# PWR.net
KiCad netlist of a schematic drawn in Altium Designer
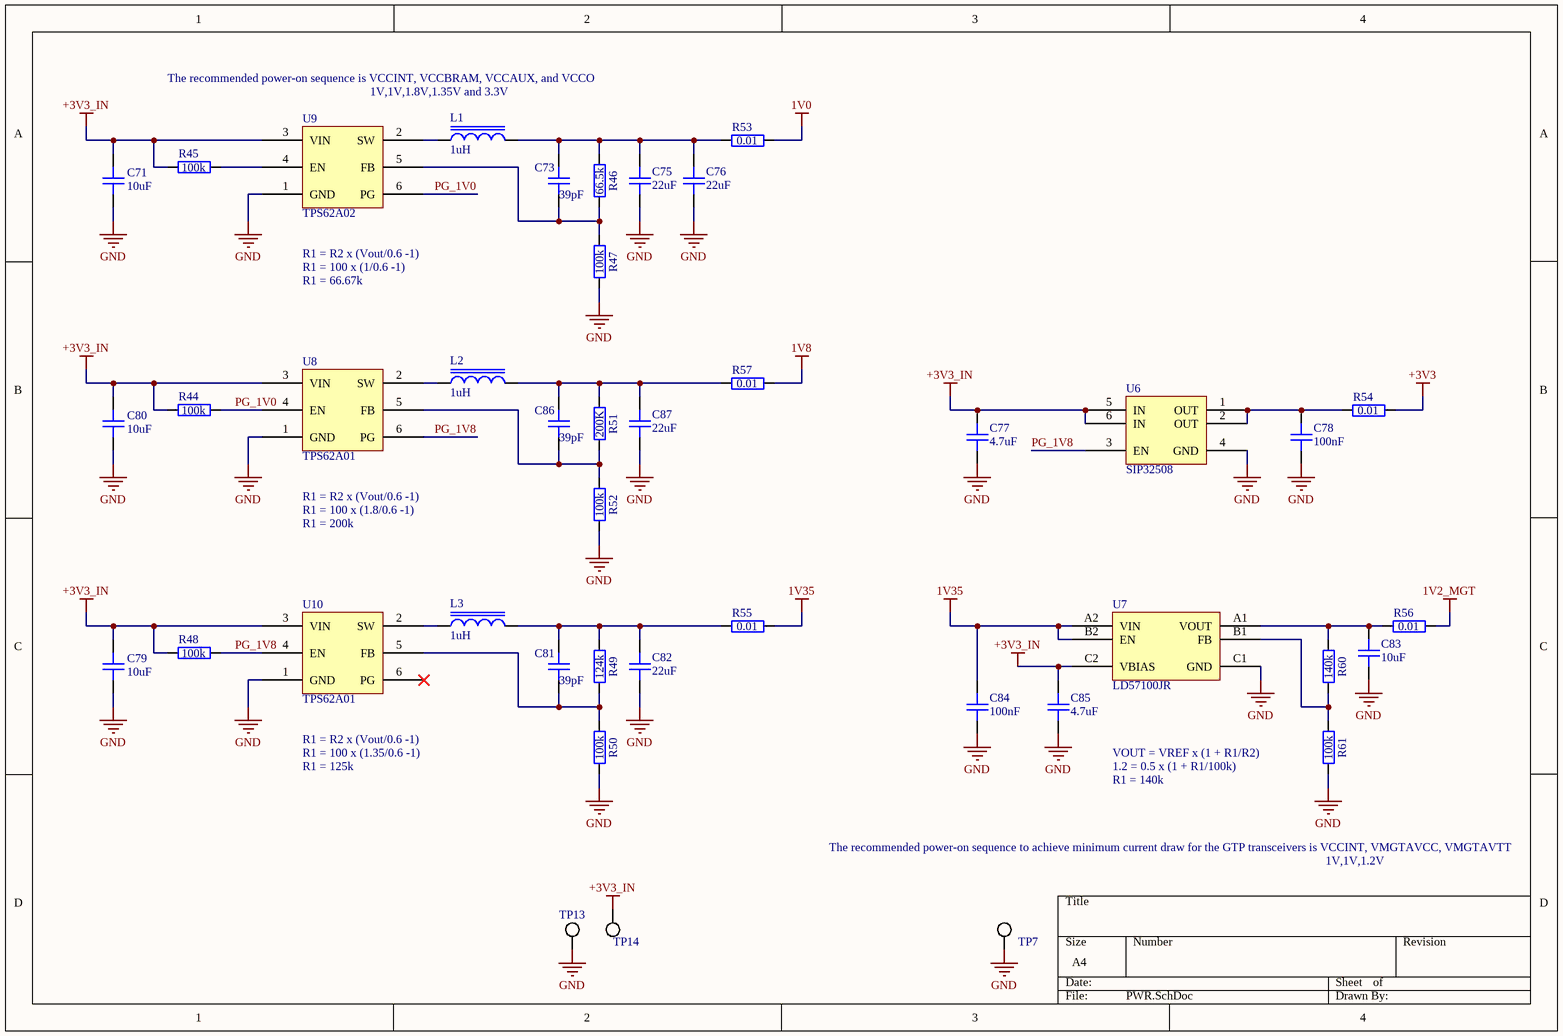
[diagram p0: PWR.SchDoc]

(export (version "E")
  (design (tool "Eeschema 10.0.6"))
  (components
    (comp (ref "C71")
      (value "10uF")
      (footprint "GEN_C_0603")
      (fields
        (field (name "HOUSE PART NUMBER") "C-10uF-0603-002")
        (field (name "MANUFACTURER") "Murata")
        (field (name "MANUFACTURER PART NUMBER") "GRM188R61A106ME69D")
      )
      (libsource (lib "DSO") (part "CAP 10uF 10V X5R 0603"))
    )
    (comp (ref "C73")
      (value "39pF")
      (footprint "GEN_C_0402")
      (fields
        (field (name "HOUSE PART NUMBER") "C-39pF-0402-002")
        (field (name "MANUFACTURER") "KEMET")
        (field (name "MANUFACTURER PART NUMBER") "C0402C390J5GACTU")
      )
      (libsource (lib "DSO") (part "CAP 39pF 50V C0G 0402"))
    )
    (comp (ref "C75")
      (value "22uF")
      (footprint "GEN_C_0805")
      (fields
        (field (name "HOUSE PART NUMBER") "C-22uF-0805-002")
        (field (name "MANUFACTURER") "Murata")
        (field (name "MANUFACTURER PART NUMBER") "GRM21BR61E226ME44L")
      )
      (libsource (lib "DSO") (part "CAP 22uF 25V X5R 0805"))
    )
    (comp (ref "C76")
      (value "22uF")
      (footprint "GEN_C_0805")
      (fields
        (field (name "HOUSE PART NUMBER") "C-22uF-0805-002")
        (field (name "MANUFACTURER") "Murata")
        (field (name "MANUFACTURER PART NUMBER") "GRM21BR61E226ME44L")
      )
      (libsource (lib "DSO") (part "CAP 22uF 25V X5R 0805"))
    )
    (comp (ref "C77")
      (value "4.7uF")
      (footprint "GEN_C_0402")
      (fields
        (field (name "HOUSE PART NUMBER") "C-4.7uF-0402-002")
        (field (name "MANUFACTURER") "Murata")
        (field (name "MANUFACTURER PART NUMBER") "GRM155R60J475ME47D")
      )
      (libsource (lib "DSO") (part "CAP 4.7uF 6.3V X5R 0402"))
    )
    (comp (ref "C78")
      (value "100nF")
      (footprint "GEN_C_0402")
      (fields
        (field (name "HOUSE PART NUMBER") "C-100nF-0402-002")
        (field (name "MANUFACTURER") "Murata")
        (field (name "MANUFACTURER PART NUMBER") "GCM155R71C104KA55D")
      )
      (libsource (lib "DSO") (part "CAP 100nF 16V X7R 0402"))
    )
    (comp (ref "C79")
      (value "10uF")
      (footprint "GEN_C_0603")
      (fields
        (field (name "HOUSE PART NUMBER") "C-10uF-0603-002")
        (field (name "MANUFACTURER") "Murata")
        (field (name "MANUFACTURER PART NUMBER") "GRM188R61A106ME69D")
      )
      (libsource (lib "DSO") (part "CAP 10uF 10V X5R 0603"))
    )
    (comp (ref "C80")
      (value "10uF")
      (footprint "GEN_C_0603")
      (fields
        (field (name "HOUSE PART NUMBER") "C-10uF-0603-002")
        (field (name "MANUFACTURER") "Murata")
        (field (name "MANUFACTURER PART NUMBER") "GRM188R61A106ME69D")
      )
      (libsource (lib "DSO") (part "CAP 10uF 10V X5R 0603"))
    )
    (comp (ref "C81")
      (value "39pF")
      (footprint "GEN_C_0402")
      (fields
        (field (name "HOUSE PART NUMBER") "C-39pF-0402-002")
        (field (name "MANUFACTURER") "KEMET")
        (field (name "MANUFACTURER PART NUMBER") "C0402C390J5GACTU")
      )
      (libsource (lib "DSO") (part "CAP 39pF 50V C0G 0402"))
    )
    (comp (ref "C82")
      (value "22uF")
      (footprint "GEN_C_0805")
      (fields
        (field (name "HOUSE PART NUMBER") "C-22uF-0805-002")
        (field (name "MANUFACTURER") "Murata")
        (field (name "MANUFACTURER PART NUMBER") "GRM21BR61E226ME44L")
      )
      (libsource (lib "DSO") (part "CAP 22uF 25V X5R 0805"))
    )
    (comp (ref "C83")
      (value "10uF")
      (footprint "GEN_C_0603")
      (fields
        (field (name "HOUSE PART NUMBER") "C-10uF-0603-002")
        (field (name "MANUFACTURER") "Murata")
        (field (name "MANUFACTURER PART NUMBER") "GRM188R61A106ME69D")
      )
      (libsource (lib "DSO") (part "CAP 10uF 10V X5R 0603"))
    )
    (comp (ref "C84")
      (value "100nF")
      (footprint "GEN_C_0402")
      (fields
        (field (name "HOUSE PART NUMBER") "C-100nF-0402-002")
        (field (name "MANUFACTURER") "Murata")
        (field (name "MANUFACTURER PART NUMBER") "GCM155R71C104KA55D")
      )
      (libsource (lib "DSO") (part "CAP 100nF 16V X7R 0402"))
    )
    (comp (ref "C85")
      (value "4.7uF")
      (footprint "GEN_C_0402")
      (fields
        (field (name "HOUSE PART NUMBER") "C-4.7uF-0402-002")
        (field (name "MANUFACTURER") "Murata")
        (field (name "MANUFACTURER PART NUMBER") "GRM155R60J475ME47D")
      )
      (libsource (lib "DSO") (part "CAP 4.7uF 6.3V X5R 0402"))
    )
    (comp (ref "C86")
      (value "39pF")
      (footprint "GEN_C_0402")
      (fields
        (field (name "HOUSE PART NUMBER") "C-39pF-0402-002")
        (field (name "MANUFACTURER") "KEMET")
        (field (name "MANUFACTURER PART NUMBER") "C0402C390J5GACTU")
      )
      (libsource (lib "DSO") (part "CAP 39pF 50V C0G 0402"))
    )
    (comp (ref "C87")
      (value "22uF")
      (footprint "GEN_C_0805")
      (fields
        (field (name "HOUSE PART NUMBER") "C-22uF-0805-002")
        (field (name "MANUFACTURER") "Murata")
        (field (name "MANUFACTURER PART NUMBER") "GRM21BR61E226ME44L")
      )
      (libsource (lib "DSO") (part "CAP 22uF 25V X5R 0805"))
    )
    (comp (ref "L1")
      (value "1uH")
      (footprint "GEN_L_1210")
      (fields (field (name "HOUSE PART NUMBER") "SRP3212-1R0M") (field (name "MANUFACTURER") "Bourns"))
      (libsource (lib "DSO") (part "IND 1uH 5.5A 32 MOHM 1210"))
    )
    (comp (ref "L2")
      (value "1uH")
      (footprint "GEN_L_1210")
      (fields (field (name "HOUSE PART NUMBER") "SRP3212-1R0M") (field (name "MANUFACTURER") "Bourns"))
      (libsource (lib "DSO") (part "IND 1uH 5.5A 32 MOHM 1210"))
    )
    (comp (ref "L3")
      (value "1uH")
      (footprint "GEN_L_1210")
      (fields (field (name "HOUSE PART NUMBER") "SRP3212-1R0M") (field (name "MANUFACTURER") "Bourns"))
      (libsource (lib "DSO") (part "IND 1uH 5.5A 32 MOHM 1210"))
    )
    (comp (ref "R44")
      (value "100k")
      (footprint "GEN_R_0402")
      (fields
        (field (name "TOLERANCE") "1%")
        (field (name "HOUSE PART NUMBER") "R-100K-0402-1%-001")
        (field (name "MANUFACTURER") "Yageo")
      )
      (libsource (lib "") (part "RES 100K OHM 1% 1/10W 0402_1"))
    )
    (comp (ref "R45")
      (value "100k")
      (footprint "GEN_R_0402")
      (fields
        (field (name "TOLERANCE") "1%")
        (field (name "HOUSE PART NUMBER") "R-100K-0402-1%-001")
        (field (name "MANUFACTURER") "Yageo")
      )
      (libsource (lib "") (part "RES 100K OHM 1% 1/10W 0402_1"))
    )
    (comp (ref "R46")
      (value "66.5k")
      (footprint "GEN_R_0402")
      (fields
        (field (name "TOLERANCE") "1%")
        (field (name "HOUSE PART NUMBER") "R-66.5K-0402-1%-001")
        (field (name "MANUFACTURER") "Yageo")
      )
      (libsource (lib "DSO") (part "RES 66.5K OHM 1% 1/16W 0402"))
    )
    (comp (ref "R47")
      (value "100k")
      (footprint "GEN_R_0402")
      (fields
        (field (name "TOLERANCE") "1%")
        (field (name "HOUSE PART NUMBER") "R-100K-0402-1%-001")
        (field (name "MANUFACTURER") "Yageo")
      )
      (libsource (lib "DSO") (part "RES 100K OHM 1% 1/10W 0402"))
    )
    (comp (ref "R48")
      (value "100k")
      (footprint "GEN_R_0402")
      (fields
        (field (name "TOLERANCE") "1%")
        (field (name "HOUSE PART NUMBER") "R-100K-0402-1%-001")
        (field (name "MANUFACTURER") "Yageo")
      )
      (libsource (lib "") (part "RES 100K OHM 1% 1/10W 0402_1"))
    )
    (comp (ref "R49")
      (value "124k")
      (footprint "GEN_R_0402")
      (fields
        (field (name "TOLERANCE") "1%")
        (field (name "HOUSE PART NUMBER") "R-124K-0402-1%-001")
        (field (name "MANUFACTURER") "Yageo")
      )
      (libsource (lib "DSO") (part "RES 124K OHM 1% 1/10W 0402"))
    )
    (comp (ref "R50")
      (value "100k")
      (footprint "GEN_R_0402")
      (fields
        (field (name "TOLERANCE") "1%")
        (field (name "HOUSE PART NUMBER") "R-100K-0402-1%-001")
        (field (name "MANUFACTURER") "Yageo")
      )
      (libsource (lib "DSO") (part "RES 100K OHM 1% 1/10W 0402"))
    )
    (comp (ref "R51")
      (value "200K")
      (footprint "GEN_R_0402")
      (fields
        (field (name "TOLERANCE") "1%")
        (field (name "HOUSE PART NUMBER") "R-200K-0402-1%-001")
        (field (name "MANUFACTURER") "Yageo")
      )
      (libsource (lib "DSO") (part "RES 200K OHM 1% 1/16W 0402"))
    )
    (comp (ref "R52")
      (value "100k")
      (footprint "GEN_R_0402")
      (fields
        (field (name "TOLERANCE") "1%")
        (field (name "HOUSE PART NUMBER") "R-100K-0402-1%-001")
        (field (name "MANUFACTURER") "Yageo")
      )
      (libsource (lib "DSO") (part "RES 100K OHM 1% 1/10W 0402"))
    )
    (comp (ref "R53")
      (value "0.01")
      (footprint "GEN_R_0603")
      (fields
        (field (name "TOLERANCE") "1%")
        (field (name "HOUSE PART NUMBER") "R-0.01-0603-1%-001")
        (field (name "MANUFACTURER") "Susumu")
      )
      (libsource (lib "DSO") (part "RES 0.01 OHM 1% 1/4W 0603"))
    )
    (comp (ref "R54")
      (value "0.01")
      (footprint "GEN_R_0603")
      (fields
        (field (name "TOLERANCE") "1%")
        (field (name "HOUSE PART NUMBER") "R-0.01-0603-1%-001")
        (field (name "MANUFACTURER") "Susumu")
      )
      (libsource (lib "DSO") (part "RES 0.01 OHM 1% 1/4W 0603"))
    )
    (comp (ref "R55")
      (value "0.01")
      (footprint "GEN_R_0603")
      (fields
        (field (name "TOLERANCE") "1%")
        (field (name "HOUSE PART NUMBER") "R-0.01-0603-1%-001")
        (field (name "MANUFACTURER") "Susumu")
      )
      (libsource (lib "DSO") (part "RES 0.01 OHM 1% 1/4W 0603"))
    )
    (comp (ref "R56")
      (value "0.01")
      (footprint "GEN_R_0603")
      (fields
        (field (name "TOLERANCE") "1%")
        (field (name "HOUSE PART NUMBER") "R-0.01-0603-1%-001")
        (field (name "MANUFACTURER") "Susumu")
      )
      (libsource (lib "DSO") (part "RES 0.01 OHM 1% 1/4W 0603"))
    )
    (comp (ref "R57")
      (value "0.01")
      (footprint "GEN_R_0603")
      (fields
        (field (name "TOLERANCE") "1%")
        (field (name "HOUSE PART NUMBER") "R-0.01-0603-1%-001")
        (field (name "MANUFACTURER") "Susumu")
      )
      (libsource (lib "DSO") (part "RES 0.01 OHM 1% 1/4W 0603"))
    )
    (comp (ref "R60")
      (value "140k")
      (footprint "GEN_R_0402")
      (fields
        (field (name "TOLERANCE") "1%")
        (field (name "HOUSE PART NUMBER") "R-140K-0402-1%-001")
        (field (name "MANUFACTURER") "Yageo")
      )
      (libsource (lib "DSO") (part "RES 140K OHM 1% 1/10W 0402"))
    )
    (comp (ref "R61")
      (value "100k")
      (footprint "GEN_R_0402")
      (fields
        (field (name "TOLERANCE") "1%")
        (field (name "HOUSE PART NUMBER") "R-100K-0402-1%-001")
        (field (name "MANUFACTURER") "Yageo")
      )
      (libsource (lib "DSO") (part "RES 100K OHM 1% 1/10W 0402"))
    )
    (comp (ref "TP7") (value "PCB") (footprint "GEN_TP_PCB") (libsource (lib "DSO") (part "TP PCB 1mm")))
    (comp (ref "TP13") (value "PCB") (footprint "GEN_TP_PCB") (libsource (lib "DSO") (part "TP PCB 1mm")))
    (comp (ref "TP14") (value "PCB") (footprint "GEN_TP_PCB") (libsource (lib "DSO") (part "TP PCB 1mm")))
    (comp (ref "U6")
      (value "SIP32508")
      (footprint "VISH_TSOT6")
      (fields
        (field (name "MANUFACTURER") "Vishay Siliconix")
        (field (name "MANUFACTURER PART NUMBER") "SIP32508DT-T1-GE3")
      )
      (libsource (lib "DSO") (part "IC SWITCH LOAD SIP32508"))
    )
    (comp (ref "U7")
      (value "LD57100JR")
      (footprint "ST_FlipChip6")
      (fields (field (name "MANUFACTURER") "STMicroelectronics"))
      (libsource (lib "DSO") (part "IC LDO LD57100JR"))
    )
    (comp (ref "U8")
      (value "TPS62A01")
      (footprint "TI_SOT563_DRL0006A")
      (fields
        (field (name "HOUSE PART NUMBER") "TPS62A01DRLR")
        (field (name "MANUFACTURER") "Texas Instruments")
      )
      (libsource (lib "DSO") (part "IC BUCK TPS62A01"))
    )
    (comp (ref "U9")
      (value "TPS62A02")
      (footprint "TI_SOT563_DRL0006A")
      (fields
        (field (name "HOUSE PART NUMBER") "TPS62A02DRLR")
        (field (name "MANUFACTURER") "Texas Instruments")
      )
      (libsource (lib "DSO") (part "IC BUCK TPS62A02"))
    )
    (comp (ref "U10")
      (value "TPS62A01")
      (footprint "TI_SOT563_DRL0006A")
      (fields
        (field (name "HOUSE PART NUMBER") "TPS62A01DRLR")
        (field (name "MANUFACTURER") "Texas Instruments")
      )
      (libsource (lib "DSO") (part "IC BUCK TPS62A01"))
    )
  )
  (nets
    (net (code "1") (name "+3V3") (class "Default")
      (node (ref "R54") (pin "2") (pinfunction "2_2") (pintype "passive"))
    )
    (net (code "2") (name "+3V3_IN") (class "Default")
      (node (ref "C71") (pin "2") (pinfunction "2_2") (pintype "passive"))
      (node (ref "C77") (pin "2") (pinfunction "2_2") (pintype "passive"))
      (node (ref "C79") (pin "2") (pinfunction "2_2") (pintype "passive"))
      (node (ref "C80") (pin "2") (pinfunction "2_2") (pintype "passive"))
      (node (ref "C85") (pin "2") (pinfunction "2_2") (pintype "passive"))
      (node (ref "R44") (pin "2") (pinfunction "2_2") (pintype "passive"))
      (node (ref "R45") (pin "2") (pinfunction "2_2") (pintype "passive"))
      (node (ref "R48") (pin "2") (pinfunction "2_2") (pintype "passive"))
      (node (ref "TP14") (pin "1") (pinfunction "1_1") (pintype "passive"))
      (node (ref "U10") (pin "3") (pinfunction "VIN_3") (pintype "power_in"))
      (node (ref "U6") (pin "5") (pinfunction "IN_5") (pintype "passive"))
      (node (ref "U6") (pin "6") (pinfunction "IN_6") (pintype "passive"))
      (node (ref "U7") (pin "C2") (pinfunction "VBIAS_C2") (pintype "passive"))
      (node (ref "U8") (pin "3") (pinfunction "VIN_3") (pintype "power_in"))
      (node (ref "U9") (pin "3") (pinfunction "VIN_3") (pintype "power_in"))
    )
    (net (code "3") (name "/PG_1V0") (class "Default")
      (node (ref "R44") (pin "1") (pinfunction "1_1") (pintype "passive"))
      (node (ref "U8") (pin "4") (pinfunction "EN_4") (pintype "passive"))
      (node (ref "U9") (pin "6") (pinfunction "PG_6") (pintype "passive"))
    )
    (net (code "4") (name "/PG_1V8") (class "Default")
      (node (ref "R48") (pin "1") (pinfunction "1_1") (pintype "passive"))
      (node (ref "U10") (pin "4") (pinfunction "EN_4") (pintype "passive"))
      (node (ref "U6") (pin "3") (pinfunction "EN_3") (pintype "passive"))
      (node (ref "U8") (pin "6") (pinfunction "PG_6") (pintype "passive"))
    )
    (net (code "5") (name "1V0") (class "Default")
      (node (ref "R53") (pin "2") (pinfunction "2_2") (pintype "passive"))
    )
    (net (code "6") (name "1V2_MGT") (class "Default")
      (node (ref "R56") (pin "2") (pinfunction "2_2") (pintype "passive"))
    )
    (net (code "7") (name "1V8") (class "Default")
      (node (ref "R57") (pin "2") (pinfunction "2_2") (pintype "passive"))
    )
    (net (code "8") (name "1V35") (class "Default")
      (node (ref "C84") (pin "2") (pinfunction "2_2") (pintype "passive"))
      (node (ref "R55") (pin "2") (pinfunction "2_2") (pintype "passive"))
      (node (ref "U7") (pin "A2") (pinfunction "VIN_A2") (pintype "passive"))
      (node (ref "U7") (pin "B2") (pinfunction "EN_B2") (pintype "passive"))
    )
    (net (code "9") (name "GND") (class "Default")
      (node (ref "C71") (pin "1") (pinfunction "1_1") (pintype "passive"))
      (node (ref "C75") (pin "1") (pinfunction "1_1") (pintype "passive"))
      (node (ref "C76") (pin "1") (pinfunction "1_1") (pintype "passive"))
      (node (ref "C77") (pin "1") (pinfunction "1_1") (pintype "passive"))
      (node (ref "C78") (pin "1") (pinfunction "1_1") (pintype "passive"))
      (node (ref "C79") (pin "1") (pinfunction "1_1") (pintype "passive"))
      (node (ref "C80") (pin "1") (pinfunction "1_1") (pintype "passive"))
      (node (ref "C82") (pin "1") (pinfunction "1_1") (pintype "passive"))
      (node (ref "C83") (pin "1") (pinfunction "1_1") (pintype "passive"))
      (node (ref "C84") (pin "1") (pinfunction "1_1") (pintype "passive"))
      (node (ref "C85") (pin "1") (pinfunction "1_1") (pintype "passive"))
      (node (ref "C87") (pin "1") (pinfunction "1_1") (pintype "passive"))
      (node (ref "R47") (pin "1") (pinfunction "1_1") (pintype "passive"))
      (node (ref "R50") (pin "1") (pinfunction "1_1") (pintype "passive"))
      (node (ref "R52") (pin "1") (pinfunction "1_1") (pintype "passive"))
      (node (ref "R61") (pin "1") (pinfunction "1_1") (pintype "passive"))
      (node (ref "TP13") (pin "1") (pinfunction "1_1") (pintype "passive"))
      (node (ref "TP7") (pin "1") (pinfunction "1_1") (pintype "passive"))
      (node (ref "U10") (pin "1") (pinfunction "GND_1") (pintype "power_in"))
      (node (ref "U6") (pin "4") (pinfunction "GND_4") (pintype "passive"))
      (node (ref "U7") (pin "C1") (pinfunction "GND_C1") (pintype "passive"))
      (node (ref "U8") (pin "1") (pinfunction "GND_1") (pintype "power_in"))
      (node (ref "U9") (pin "1") (pinfunction "GND_1") (pintype "power_in"))
    )
    (net (code "10") (name "Net-(C73-Pad2)") (class "Default")
      (node (ref "C73") (pin "2") (pinfunction "2_2") (pintype "passive"))
      (node (ref "C75") (pin "2") (pinfunction "2_2") (pintype "passive"))
      (node (ref "C76") (pin "2") (pinfunction "2_2") (pintype "passive"))
      (node (ref "L1") (pin "2") (pinfunction "2_2") (pintype "passive"))
      (node (ref "R46") (pin "2") (pinfunction "2_2") (pintype "passive"))
      (node (ref "R53") (pin "1") (pinfunction "1_1") (pintype "passive"))
    )
    (net (code "11") (name "Net-(C78-Pad2)") (class "Default")
      (node (ref "C78") (pin "2") (pinfunction "2_2") (pintype "passive"))
      (node (ref "R54") (pin "1") (pinfunction "1_1") (pintype "passive"))
      (node (ref "U6") (pin "1") (pinfunction "OUT_1") (pintype "passive"))
      (node (ref "U6") (pin "2") (pinfunction "OUT_2") (pintype "passive"))
    )
    (net (code "12") (name "Net-(C81-Pad2)") (class "Default")
      (node (ref "C81") (pin "2") (pinfunction "2_2") (pintype "passive"))
      (node (ref "C82") (pin "2") (pinfunction "2_2") (pintype "passive"))
      (node (ref "L3") (pin "2") (pinfunction "2_2") (pintype "passive"))
      (node (ref "R49") (pin "2") (pinfunction "2_2") (pintype "passive"))
      (node (ref "R55") (pin "1") (pinfunction "1_1") (pintype "passive"))
    )
    (net (code "13") (name "Net-(C86-Pad2)") (class "Default")
      (node (ref "C86") (pin "2") (pinfunction "2_2") (pintype "passive"))
      (node (ref "C87") (pin "2") (pinfunction "2_2") (pintype "passive"))
      (node (ref "L2") (pin "2") (pinfunction "2_2") (pintype "passive"))
      (node (ref "R51") (pin "2") (pinfunction "2_2") (pintype "passive"))
      (node (ref "R57") (pin "1") (pinfunction "1_1") (pintype "passive"))
    )
    (net (code "14") (name "Net-(U7-FB)") (class "Default")
      (node (ref "R60") (pin "1") (pinfunction "1_1") (pintype "passive"))
      (node (ref "R61") (pin "2") (pinfunction "2_2") (pintype "passive"))
      (node (ref "U7") (pin "B1") (pinfunction "FB_B1") (pintype "passive"))
    )
    (net (code "15") (name "Net-(U7-VOUT)") (class "Default")
      (node (ref "C83") (pin "2") (pinfunction "2_2") (pintype "passive"))
      (node (ref "R56") (pin "1") (pinfunction "1_1") (pintype "passive"))
      (node (ref "R60") (pin "2") (pinfunction "2_2") (pintype "passive"))
      (node (ref "U7") (pin "A1") (pinfunction "VOUT_A1") (pintype "passive"))
    )
    (net (code "16") (name "Net-(U8-FB)") (class "Default")
      (node (ref "C86") (pin "1") (pinfunction "1_1") (pintype "passive"))
      (node (ref "R51") (pin "1") (pinfunction "1_1") (pintype "passive"))
      (node (ref "R52") (pin "2") (pinfunction "2_2") (pintype "passive"))
      (node (ref "U8") (pin "5") (pinfunction "FB_5") (pintype "passive"))
    )
    (net (code "17") (name "Net-(U8-SW)") (class "Default")
      (node (ref "L2") (pin "1") (pinfunction "1_1") (pintype "passive"))
      (node (ref "U8") (pin "2") (pinfunction "SW_2") (pintype "passive"))
    )
    (net (code "18") (name "Net-(U9-EN)") (class "Default")
      (node (ref "R45") (pin "1") (pinfunction "1_1") (pintype "passive"))
      (node (ref "U9") (pin "4") (pinfunction "EN_4") (pintype "passive"))
    )
    (net (code "19") (name "Net-(U9-FB)") (class "Default")
      (node (ref "C73") (pin "1") (pinfunction "1_1") (pintype "passive"))
      (node (ref "R46") (pin "1") (pinfunction "1_1") (pintype "passive"))
      (node (ref "R47") (pin "2") (pinfunction "2_2") (pintype "passive"))
      (node (ref "U9") (pin "5") (pinfunction "FB_5") (pintype "passive"))
    )
    (net (code "20") (name "Net-(U9-SW)") (class "Default")
      (node (ref "L1") (pin "1") (pinfunction "1_1") (pintype "passive"))
      (node (ref "U9") (pin "2") (pinfunction "SW_2") (pintype "passive"))
    )
    (net (code "21") (name "Net-(U10-FB)") (class "Default")
      (node (ref "C81") (pin "1") (pinfunction "1_1") (pintype "passive"))
      (node (ref "R49") (pin "1") (pinfunction "1_1") (pintype "passive"))
      (node (ref "R50") (pin "2") (pinfunction "2_2") (pintype "passive"))
      (node (ref "U10") (pin "5") (pinfunction "FB_5") (pintype "passive"))
    )
    (net (code "22") (name "Net-(U10-SW)") (class "Default")
      (node (ref "L3") (pin "1") (pinfunction "1_1") (pintype "passive"))
      (node (ref "U10") (pin "2") (pinfunction "SW_2") (pintype "passive"))
    )
    (net (code "23") (name "unconnected-(U10-PG-Pad6)") (class "Default")
      (node (ref "U10") (pin "6") (pinfunction "PG_6") (pintype "passive+no_connect"))
    )
  )
)
